# Converter_12V-3V3.net
KiCad netlist of a schematic drawn in Altium Designer
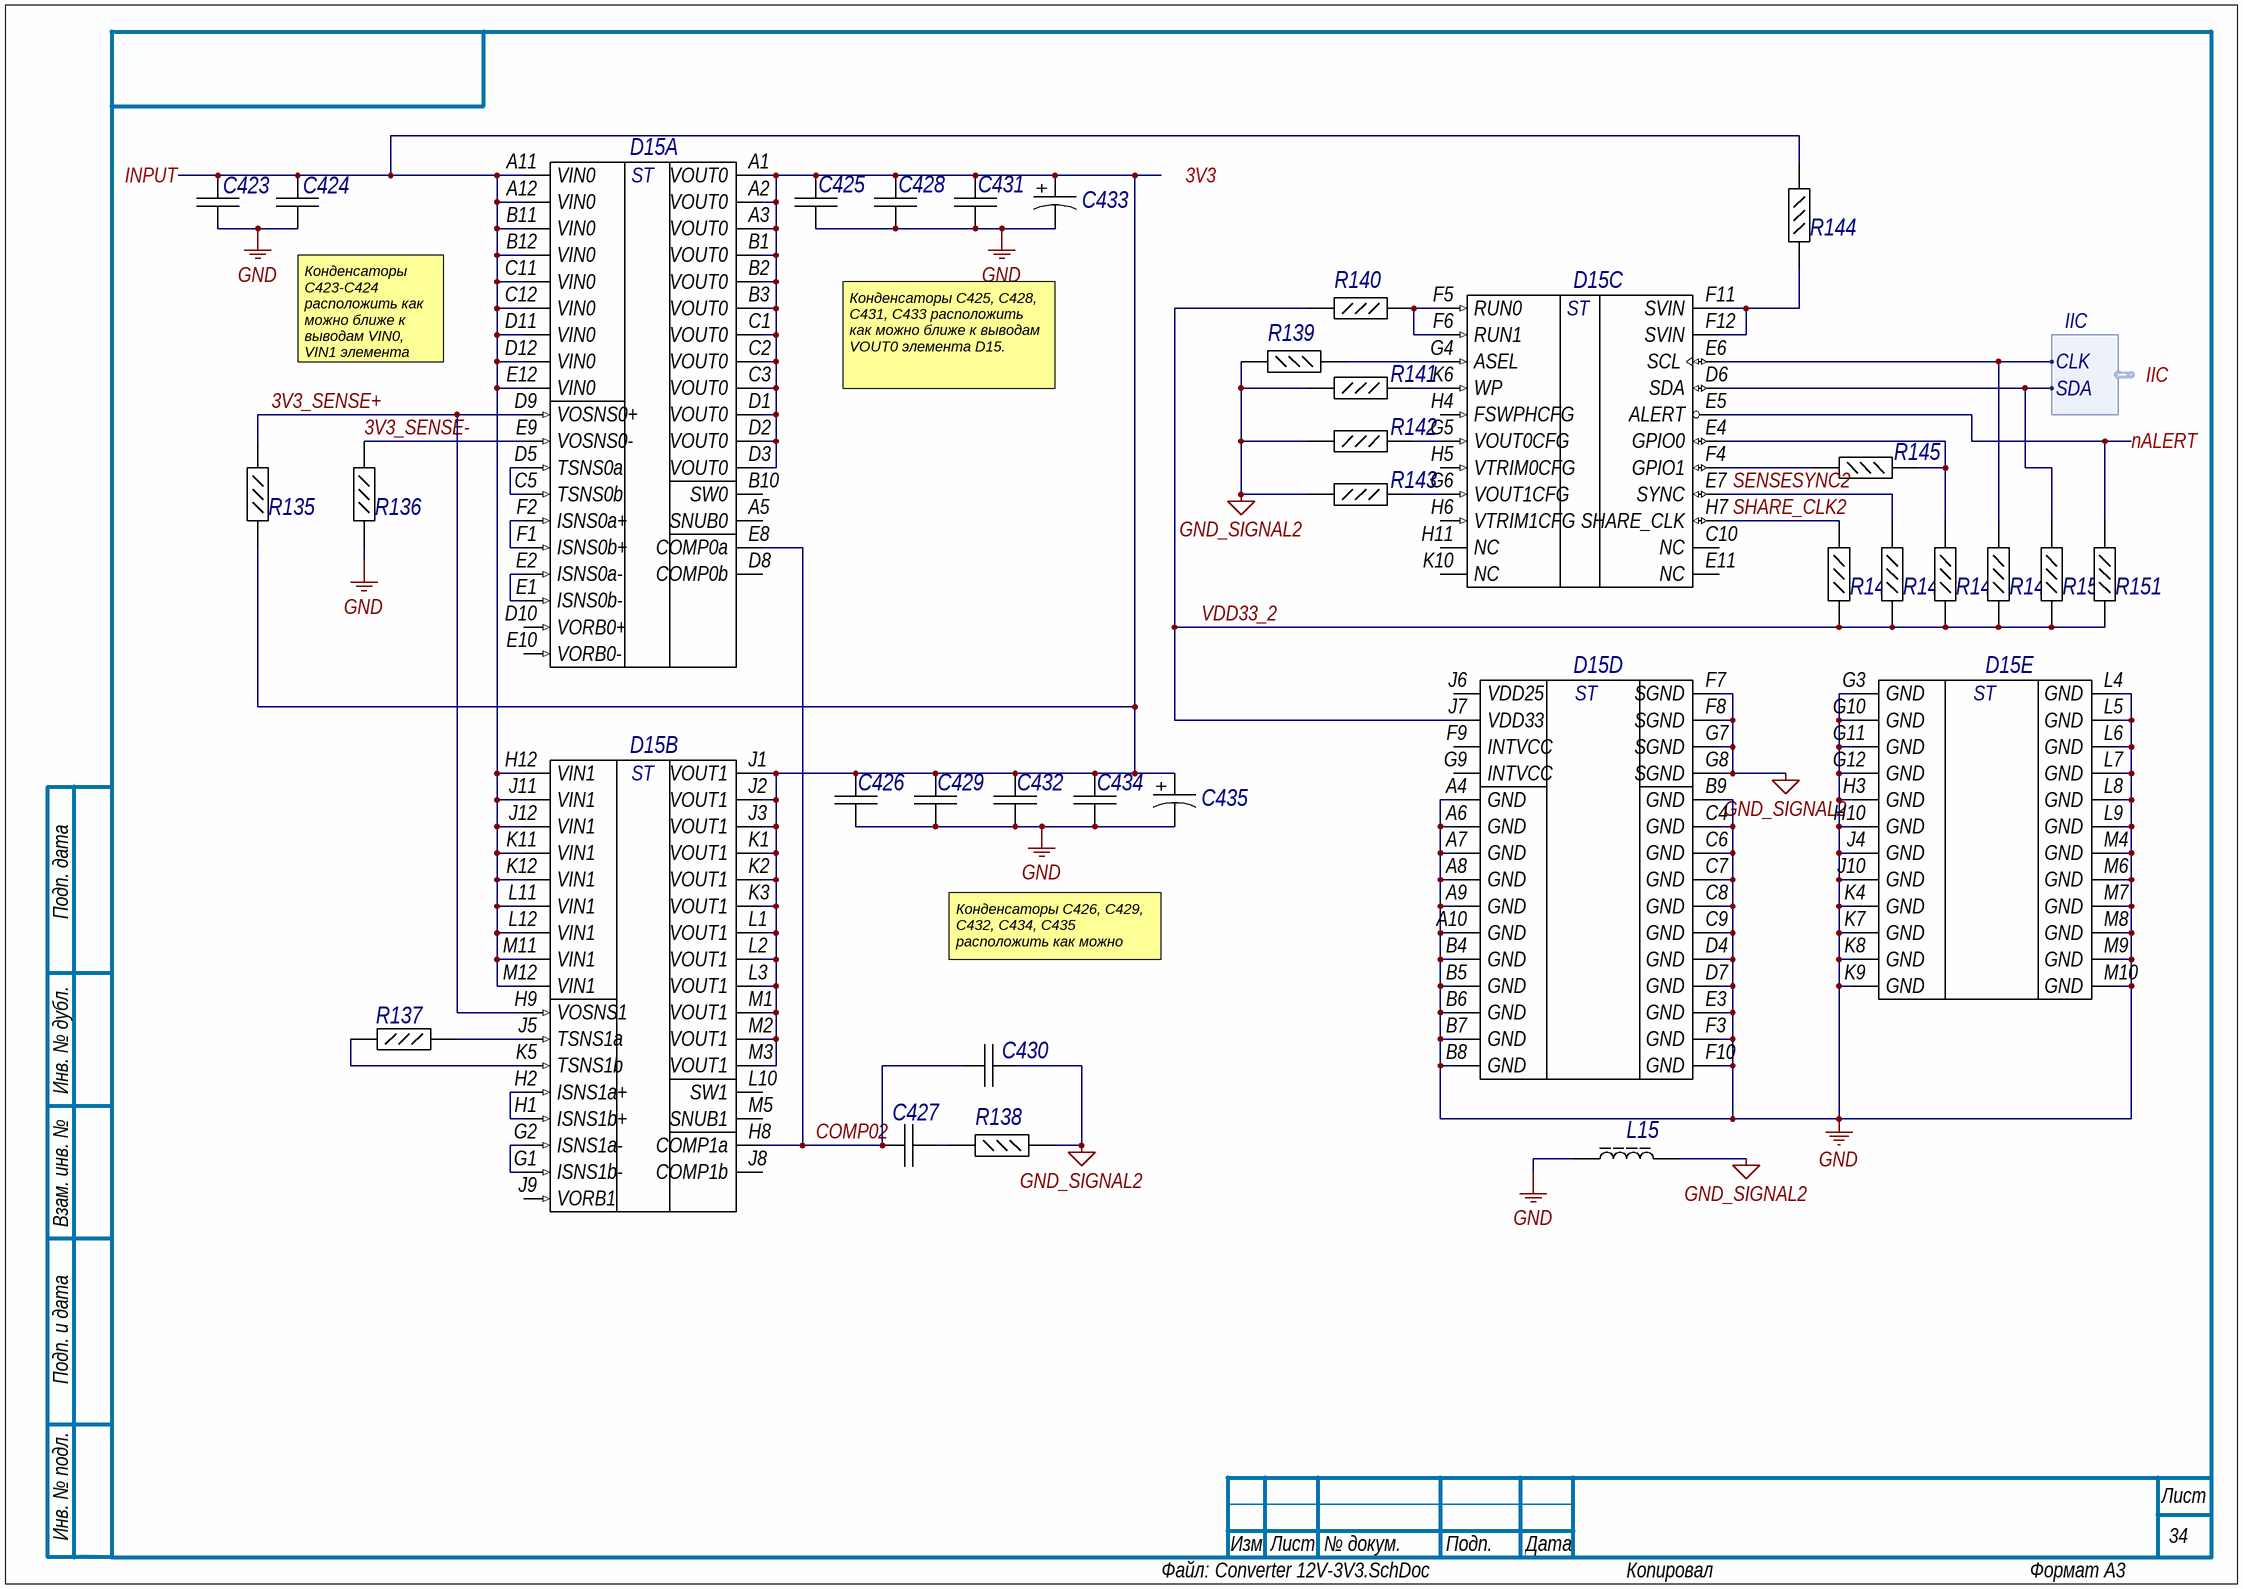
[diagram p0: Converter 12V-3V3.SchDoc]

(export (version "E")
  (design (tool "Eeschema 10.0.6"))
  (components
    (comp (ref "C423")
      (value "GRM31CR61E226KE15L")
      (footprint "CAPC3216X180X55ML20T25")
      (description "Chip Capacitor, 22 uF, +/- 10%, 25 V, -55 to 85 degC, 1206 (3216 Metric), RoHS, Tape and Reel")
      (fields (field (name "TOLERANCE") "10%"))
      (libsource (lib "MiniPC DB") (part "CAP_NP"))
    )
    (comp (ref "C424")
      (value "GRM31CR61E226KE15L")
      (footprint "CAPC3216X180X55ML20T25")
      (description "Chip Capacitor, 22 uF, +/- 10%, 25 V, -55 to 85 degC, 1206 (3216 Metric), RoHS, Tape and Reel")
      (fields (field (name "TOLERANCE") "10%"))
      (libsource (lib "MiniPC DB") (part "CAP_NP"))
    )
    (comp (ref "C425")
      (value "GRM31CR60J107ME39L")
      (footprint "CAPC3216X190X55ML30T25")
      (description "Chip Capacitor, 100 uF, +/- 20%, 6.3 V, -55 to 85 degC, 1206 (3216 Metric), RoHS, Tape and Reel")
      (fields (field (name "TOLERANCE") "20%"))
      (libsource (lib "MiniPC DB") (part "CAP_NP"))
    )
    (comp (ref "C426")
      (value "GRM31CR60J107ME39L")
      (footprint "CAPC3216X190X55ML30T25")
      (description "Chip Capacitor, 100 uF, +/- 20%, 6.3 V, -55 to 85 degC, 1206 (3216 Metric), RoHS, Tape and Reel")
      (fields (field (name "TOLERANCE") "20%"))
      (libsource (lib "MiniPC DB") (part "CAP_NP"))
    )
    (comp (ref "C427")
      (value "CGJ2B2X7R1E222K050BA")
      (footprint "CAPC1005X55X10ML05")
      (description "Chip Capacitor, 2.2 nF, +/- 10%, 25 V, -55 to 125 degC, 0402 (1005 Metric), RoHS, Tape and Reel")
      (fields (field (name "TOLERANCE") "10%"))
      (libsource (lib "MiniPC DB") (part "CAP_NP"))
    )
    (comp (ref "C428")
      (value "GRM31CR60J107ME39L")
      (footprint "CAPC3216X190X55ML30T25")
      (description "Chip Capacitor, 100 uF, +/- 20%, 6.3 V, -55 to 85 degC, 1206 (3216 Metric), RoHS, Tape and Reel")
      (fields (field (name "TOLERANCE") "20%"))
      (libsource (lib "MiniPC DB") (part "CAP_NP"))
    )
    (comp (ref "C429")
      (value "GRM31CR60J107ME39L")
      (footprint "CAPC3216X190X55ML30T25")
      (description "Chip Capacitor, 100 uF, +/- 20%, 6.3 V, -55 to 85 degC, 1206 (3216 Metric), RoHS, Tape and Reel")
      (fields (field (name "TOLERANCE") "20%"))
      (libsource (lib "MiniPC DB") (part "CAP_NP"))
    )
    (comp (ref "C430")
      (value "ECJ-0EC1H680J")
      (footprint "CAPC1005X55X20ML5T10")
      (description "Chip Capacitor, 68 pF, +/- 5%, 50 V, -55 to 125 degC, 0402 (1005 Metric), RoHS, Tape and Reel")
      (fields (field (name "TOLERANCE") "5%"))
      (libsource (lib "MiniPC DB") (part "CAP_NP"))
    )
    (comp (ref "C431")
      (value "GRM31CR60J107ME39L")
      (footprint "CAPC3216X190X55ML30T25")
      (description "Chip Capacitor, 100 uF, +/- 20%, 6.3 V, -55 to 85 degC, 1206 (3216 Metric), RoHS, Tape and Reel")
      (fields (field (name "TOLERANCE") "20%"))
      (libsource (lib "MiniPC DB") (part "CAP_NP"))
    )
    (comp (ref "C432")
      (value "GRM31CR60J107ME39L")
      (footprint "CAPC3216X190X55ML30T25")
      (description "Chip Capacitor, 100 uF, +/- 20%, 6.3 V, -55 to 85 degC, 1206 (3216 Metric), RoHS, Tape and Reel")
      (fields (field (name "TOLERANCE") "20%"))
      (libsource (lib "MiniPC DB") (part "CAP_NP"))
    )
    (comp (ref "C433")
      (value "6TPF330M9L")
      (footprint "PNSC-TPF-D3L_V")
      (description "Tantalum Capacitor, 330 uF, +/- 20%, 6.3 V, -55 to 105 degC, 2-Pin Molded, RoHS, Tape and Reel")
      (libsource (lib "MiniPC DB") (part "CAP_P"))
    )
    (comp (ref "C434")
      (value "GRM31CR60J107ME39L")
      (footprint "CAPC3216X190X55ML30T25")
      (description "Chip Capacitor, 100 uF, +/- 20%, 6.3 V, -55 to 85 degC, 1206 (3216 Metric), RoHS, Tape and Reel")
      (fields (field (name "TOLERANCE") "20%"))
      (libsource (lib "MiniPC DB") (part "CAP_NP"))
    )
    (comp (ref "C435")
      (value "6TPF330M9L")
      (footprint "PNSC-TPF-D3L_V")
      (description "Tantalum Capacitor, 330 uF, +/- 20%, 6.3 V, -55 to 105 degC, 2-Pin Molded, RoHS, Tape and Reel")
      (libsource (lib "MiniPC DB") (part "CAP_P"))
    )
    (comp (ref "D15")
      (value "LTM4676IY#PBF")
      (footprint "LT-BGA-144-05-08-1920_V")
      (libsource (lib "MiniPC DB") (part "LTM4676"))
    )
    (comp (ref "L15")
      (value "742792609")
      (footprint "SMD-0603")
      (description "SMD EMI Suppression Ferrite Bead WE-CBF, Z = 30 Ohm")
      (libsource (lib "MiniPC DB") (part "Choke"))
    )
    (comp (ref "R135")
      (value "ERJ-2GE0R00X")
      (footprint "RESC1005X40X25LL05T05")
      (description "Chip Resistor, 0 mOhm, +/- 5%, 100 mW, -55 to 155 degC, 0402 (1005 Metric), RoHS, Tape and Reel")
      (fields (field (name "TOLERANCE") "5%") (field (name "MANUFACTURER") "Basic Passives"))
      (libsource (lib "MiniPC DB") (part "RES-0.05"))
    )
    (comp (ref "R136")
      (value "ERJ-2GE0R00X")
      (footprint "RESC1005X40X25LL05T05")
      (description "Chip Resistor, 0 mOhm, +/- 5%, 100 mW, -55 to 155 degC, 0402 (1005 Metric), RoHS, Tape and Reel")
      (fields (field (name "TOLERANCE") "5%") (field (name "MANUFACTURER") "Basic Passives"))
      (libsource (lib "MiniPC DB") (part "RES-0.05"))
    )
    (comp (ref "R137")
      (value "ERJ-2GE0R00X")
      (footprint "RESC1005X40X25LL05T05")
      (description "Chip Resistor, 0 mOhm, +/- 5%, 100 mW, -55 to 155 degC, 0402 (1005 Metric), RoHS, Tape and Reel")
      (fields (field (name "TOLERANCE") "5%") (field (name "MANUFACTURER") "Basic Passives"))
      (libsource (lib "") (part "RES-0.05_2"))
    )
    (comp (ref "R138")
      (value "ERJ-2RKF4751X")
      (footprint "RESC1005X40X25LL05T05")
      (description "Chip Resistor, 4.75 KOhm, +/- 1%, 100 mW, -55 to 155 degC, 0402 (1005 Metric), RoHS, Tape and Reel")
      (fields (field (name "TOLERANCE") "1%") (field (name "MANUFACTURER") "Basic Passives"))
      (libsource (lib "MiniPC DB") (part "RES-0.05"))
    )
    (comp (ref "R139")
      (value "CRCW040222K6FKED")
      (footprint "RESC1005X40X25LL05T05")
      (description "Chip Resistor, 22.6 KOhm, +/- 1%, 63 mW, -55 to 155 degC, 0402 (1005 Metric), RoHS, Tape and Reel")
      (fields (field (name "TOLERANCE") "1%"))
      (libsource (lib "") (part "RES-0.05_1"))
    )
    (comp (ref "R140")
      (value "ERJ-2RKF1002X")
      (footprint "RESC1005X40X25LL05T05")
      (description "Chip Resistor, 10 KOhm, +/- 1%, 100 mW, -55 to 155 degC, 0402 (1005 Metric), RoHS, Tape and Reel")
      (fields (field (name "TOLERANCE") "1%") (field (name "MANUFACTURER") "Basic Passives"))
      (libsource (lib "") (part "RES-0.05_2"))
    )
    (comp (ref "R141")
      (value "ERJ-2RKF1002X")
      (footprint "RESC1005X40X25LL05T05")
      (description "Chip Resistor, 10 KOhm, +/- 1%, 100 mW, -55 to 155 degC, 0402 (1005 Metric), RoHS, Tape and Reel")
      (fields (field (name "TOLERANCE") "1%") (field (name "MANUFACTURER") "Basic Passives"))
      (libsource (lib "") (part "RES-0.05_2"))
    )
    (comp (ref "R142")
      (value "CRCW040222K6FKED")
      (footprint "RESC1005X40X25LL05T05")
      (description "Chip Resistor, 22.6 KOhm, +/- 1%, 63 mW, -55 to 155 degC, 0402 (1005 Metric), RoHS, Tape and Reel")
      (fields (field (name "TOLERANCE") "1%"))
      (libsource (lib "") (part "RES-0.05_2"))
    )
    (comp (ref "R143")
      (value "CRCW040222K6FKED")
      (footprint "RESC1005X40X25LL05T05")
      (description "Chip Resistor, 22.6 KOhm, +/- 1%, 63 mW, -55 to 155 degC, 0402 (1005 Metric), RoHS, Tape and Reel")
      (fields (field (name "TOLERANCE") "1%"))
      (libsource (lib "") (part "RES-0.05_2"))
    )
    (comp (ref "R144")
      (value "ERJ-2GE0R00X")
      (footprint "RESC1005X40X25LL05T05")
      (description "Chip Resistor, 0 mOhm, +/- 5%, 100 mW, -55 to 155 degC, 0402 (1005 Metric), RoHS, Tape and Reel")
      (fields (field (name "TOLERANCE") "5%") (field (name "MANUFACTURER") "Basic Passives"))
      (libsource (lib "") (part "RES-0.05_3"))
    )
    (comp (ref "R145")
      (value "ERJ-2GE0R00X")
      (footprint "RESC1005X40X25LL05T05")
      (description "Chip Resistor, 0 mOhm, +/- 5%, 100 mW, -55 to 155 degC, 0402 (1005 Metric), RoHS, Tape and Reel")
      (fields (field (name "TOLERANCE") "5%") (field (name "MANUFACTURER") "Basic Passives"))
      (libsource (lib "") (part "RES-0.05_1"))
    )
    (comp (ref "R146")
      (value "ERJ-2RKF1002X")
      (footprint "RESC1005X40X25LL05T05")
      (description "Chip Resistor, 10 KOhm, +/- 1%, 100 mW, -55 to 155 degC, 0402 (1005 Metric), RoHS, Tape and Reel")
      (fields (field (name "TOLERANCE") "1%") (field (name "MANUFACTURER") "Basic Passives"))
      (libsource (lib "MiniPC DB") (part "RES-0.05"))
    )
    (comp (ref "R147")
      (value "ERJ-2RKF1002X")
      (footprint "RESC1005X40X25LL05T05")
      (description "Chip Resistor, 10 KOhm, +/- 1%, 100 mW, -55 to 155 degC, 0402 (1005 Metric), RoHS, Tape and Reel")
      (fields (field (name "TOLERANCE") "1%") (field (name "MANUFACTURER") "Basic Passives"))
      (libsource (lib "MiniPC DB") (part "RES-0.05"))
    )
    (comp (ref "R148")
      (value "ERJ-2RKF1002X")
      (footprint "RESC1005X40X25LL05T05")
      (description "Chip Resistor, 10 KOhm, +/- 1%, 100 mW, -55 to 155 degC, 0402 (1005 Metric), RoHS, Tape and Reel")
      (fields (field (name "TOLERANCE") "1%") (field (name "MANUFACTURER") "Basic Passives"))
      (libsource (lib "MiniPC DB") (part "RES-0.05"))
    )
    (comp (ref "R149")
      (value "ERJ-2RKF1002X")
      (footprint "RESC1005X40X25LL05T05")
      (description "Chip Resistor, 10 KOhm, +/- 1%, 100 mW, -55 to 155 degC, 0402 (1005 Metric), RoHS, Tape and Reel")
      (fields (field (name "TOLERANCE") "1%") (field (name "MANUFACTURER") "Basic Passives"))
      (libsource (lib "MiniPC DB") (part "RES-0.05"))
    )
    (comp (ref "R150")
      (value "ERJ-2RKF1002X")
      (footprint "RESC1005X40X25LL05T05")
      (description "Chip Resistor, 10 KOhm, +/- 1%, 100 mW, -55 to 155 degC, 0402 (1005 Metric), RoHS, Tape and Reel")
      (fields (field (name "TOLERANCE") "1%") (field (name "MANUFACTURER") "Basic Passives"))
      (libsource (lib "MiniPC DB") (part "RES-0.05"))
    )
    (comp (ref "R151")
      (value "ERJ-2RKF1002X")
      (footprint "RESC1005X40X25LL05T05")
      (description "Chip Resistor, 10 KOhm, +/- 1%, 100 mW, -55 to 155 degC, 0402 (1005 Metric), RoHS, Tape and Reel")
      (fields (field (name "TOLERANCE") "1%") (field (name "MANUFACTURER") "Basic Passives"))
      (libsource (lib "MiniPC DB") (part "RES-0.05"))
    )
  )
  (nets
    (net (code "2") (name "/3V3") (class "Default")
      (node (ref "C425") (pin "2") (pinfunction "2_2") (pintype "passive"))
      (node (ref "C426") (pin "2") (pinfunction "2_2") (pintype "passive"))
      (node (ref "C428") (pin "2") (pinfunction "2_2") (pintype "passive"))
      (node (ref "C429") (pin "2") (pinfunction "2_2") (pintype "passive"))
      (node (ref "C431") (pin "2") (pinfunction "2_2") (pintype "passive"))
      (node (ref "C432") (pin "2") (pinfunction "2_2") (pintype "passive"))
      (node (ref "C433") (pin "1") (pinfunction "1_1") (pintype "passive"))
      (node (ref "C434") (pin "2") (pinfunction "2_2") (pintype "passive"))
      (node (ref "C435") (pin "1") (pinfunction "1_1") (pintype "passive"))
      (node (ref "D15") (pin "A1") (pinfunction "VOUT0_A1") (pintype "power_in"))
      (node (ref "D15") (pin "A2") (pinfunction "VOUT0_A2") (pintype "power_in"))
      (node (ref "D15") (pin "A3") (pinfunction "VOUT0_A3") (pintype "power_in"))
      (node (ref "D15") (pin "B1") (pinfunction "VOUT0_B1") (pintype "power_in"))
      (node (ref "D15") (pin "B2") (pinfunction "VOUT0_B2") (pintype "power_in"))
      (node (ref "D15") (pin "B3") (pinfunction "VOUT0_B3") (pintype "power_in"))
      (node (ref "D15") (pin "C1") (pinfunction "VOUT0_C1") (pintype "power_in"))
      (node (ref "D15") (pin "C2") (pinfunction "VOUT0_C2") (pintype "power_in"))
      (node (ref "D15") (pin "C3") (pinfunction "VOUT0_C3") (pintype "power_in"))
      (node (ref "D15") (pin "D1") (pinfunction "VOUT0_D1") (pintype "power_in"))
      (node (ref "D15") (pin "D2") (pinfunction "VOUT0_D2") (pintype "power_in"))
      (node (ref "D15") (pin "D3") (pinfunction "VOUT0_D3") (pintype "power_in"))
      (node (ref "D15") (pin "J1") (pinfunction "VOUT1_J1") (pintype "power_in"))
      (node (ref "D15") (pin "J2") (pinfunction "VOUT1_J2") (pintype "power_in"))
      (node (ref "D15") (pin "J3") (pinfunction "VOUT1_J3") (pintype "power_in"))
      (node (ref "D15") (pin "K1") (pinfunction "VOUT1_K1") (pintype "power_in"))
      (node (ref "D15") (pin "K2") (pinfunction "VOUT1_K2") (pintype "power_in"))
      (node (ref "D15") (pin "K3") (pinfunction "VOUT1_K3") (pintype "power_in"))
      (node (ref "D15") (pin "L1") (pinfunction "VOUT1_L1") (pintype "power_in"))
      (node (ref "D15") (pin "L2") (pinfunction "VOUT1_L2") (pintype "power_in"))
      (node (ref "D15") (pin "L3") (pinfunction "VOUT1_L3") (pintype "power_in"))
      (node (ref "D15") (pin "M1") (pinfunction "VOUT1_M1") (pintype "power_in"))
      (node (ref "D15") (pin "M2") (pinfunction "VOUT1_M2") (pintype "power_in"))
      (node (ref "D15") (pin "M3") (pinfunction "VOUT1_M3") (pintype "power_in"))
      (node (ref "R135") (pin "2") (pinfunction "2_2") (pintype "passive"))
    )
    (net (code "3") (name "/3V3_SENSE+") (class "Default")
      (node (ref "D15") (pin "D9") (pinfunction "VOSNS0+_D9") (pintype "input"))
      (node (ref "D15") (pin "H9") (pinfunction "VOSNS1_H9") (pintype "input"))
      (node (ref "R135") (pin "1") (pinfunction "1_1") (pintype "passive"))
    )
    (net (code "4") (name "/3V3_SENSE-") (class "Default")
      (node (ref "D15") (pin "E9") (pinfunction "VOSNS0-_E9") (pintype "input"))
      (node (ref "R136") (pin "1") (pinfunction "1_1") (pintype "passive"))
    )
    (net (code "5") (name "/COMP02") (class "Default")
      (node (ref "C427") (pin "2") (pinfunction "2_2") (pintype "passive"))
      (node (ref "C430") (pin "2") (pinfunction "2_2") (pintype "passive"))
      (node (ref "D15") (pin "E8") (pinfunction "COMP0a_E8") (pintype "passive"))
      (node (ref "D15") (pin "H8") (pinfunction "COMP1a_H8") (pintype "passive"))
    )
    (net (code "6") (name "/INPUT") (class "Default")
      (node (ref "C423") (pin "2") (pinfunction "2_2") (pintype "passive"))
      (node (ref "C424") (pin "2") (pinfunction "2_2") (pintype "passive"))
      (node (ref "D15") (pin "A11") (pinfunction "VIN0_A11") (pintype "passive"))
      (node (ref "D15") (pin "A12") (pinfunction "VIN0_A12") (pintype "passive"))
      (node (ref "D15") (pin "B11") (pinfunction "VIN0_B11") (pintype "passive"))
      (node (ref "D15") (pin "B12") (pinfunction "VIN0_B12") (pintype "passive"))
      (node (ref "D15") (pin "C11") (pinfunction "VIN0_C11") (pintype "passive"))
      (node (ref "D15") (pin "C12") (pinfunction "VIN0_C12") (pintype "passive"))
      (node (ref "D15") (pin "D11") (pinfunction "VIN0_D11") (pintype "passive"))
      (node (ref "D15") (pin "D12") (pinfunction "VIN0_D12") (pintype "passive"))
      (node (ref "D15") (pin "E12") (pinfunction "VIN0_E12") (pintype "passive"))
      (node (ref "D15") (pin "H12") (pinfunction "VIN1_H12") (pintype "passive"))
      (node (ref "D15") (pin "J11") (pinfunction "VIN1_J11") (pintype "passive"))
      (node (ref "D15") (pin "J12") (pinfunction "VIN1_J12") (pintype "passive"))
      (node (ref "D15") (pin "K11") (pinfunction "VIN1_K11") (pintype "passive"))
      (node (ref "D15") (pin "K12") (pinfunction "VIN1_K12") (pintype "passive"))
      (node (ref "D15") (pin "L11") (pinfunction "VIN1_L11") (pintype "passive"))
      (node (ref "D15") (pin "L12") (pinfunction "VIN1_L12") (pintype "passive"))
      (node (ref "D15") (pin "M11") (pinfunction "VIN1_M11") (pintype "passive"))
      (node (ref "D15") (pin "M12") (pinfunction "VIN1_M12") (pintype "passive"))
      (node (ref "R144") (pin "2") (pinfunction "2_2") (pintype "passive"))
    )
    (net (code "7") (name "/SENSESYNC2") (class "Default")
      (node (ref "D15") (pin "E7") (pinfunction "SYNC_E7") (pintype "bidirectional"))
      (node (ref "R147") (pin "1") (pinfunction "1_1") (pintype "passive"))
    )
    (net (code "8") (name "/SHARE_CLK2") (class "Default")
      (node (ref "D15") (pin "H7") (pinfunction "SHARE_CLK_H7") (pintype "bidirectional"))
      (node (ref "R146") (pin "1") (pinfunction "1_1") (pintype "passive"))
    )
    (net (code "9") (name "/VDD33_2") (class "Default")
      (node (ref "D15") (pin "J7") (pinfunction "VDD33_J7") (pintype "passive"))
      (node (ref "R140") (pin "2") (pinfunction "2_2") (pintype "passive"))
      (node (ref "R146") (pin "2") (pinfunction "2_2") (pintype "passive"))
      (node (ref "R147") (pin "2") (pinfunction "2_2") (pintype "passive"))
      (node (ref "R148") (pin "2") (pinfunction "2_2") (pintype "passive"))
      (node (ref "R149") (pin "2") (pinfunction "2_2") (pintype "passive"))
      (node (ref "R150") (pin "2") (pinfunction "2_2") (pintype "passive"))
      (node (ref "R151") (pin "2") (pinfunction "2_2") (pintype "passive"))
    )
    (net (code "10") (name "/nALERT") (class "Default")
      (node (ref "D15") (pin "E5") (pinfunction "ALERT_E5") (pintype "open_collector"))
      (node (ref "R151") (pin "1") (pinfunction "1_1") (pintype "passive"))
    )
    (net (code "12") (name "GND") (class "Default")
      (node (ref "C423") (pin "1") (pinfunction "1_1") (pintype "passive"))
      (node (ref "C424") (pin "1") (pinfunction "1_1") (pintype "passive"))
      (node (ref "C425") (pin "1") (pinfunction "1_1") (pintype "passive"))
      (node (ref "C426") (pin "1") (pinfunction "1_1") (pintype "passive"))
      (node (ref "C428") (pin "1") (pinfunction "1_1") (pintype "passive"))
      (node (ref "C429") (pin "1") (pinfunction "1_1") (pintype "passive"))
      (node (ref "C431") (pin "1") (pinfunction "1_1") (pintype "passive"))
      (node (ref "C432") (pin "1") (pinfunction "1_1") (pintype "passive"))
      (node (ref "C433") (pin "2") (pinfunction "2_2") (pintype "passive"))
      (node (ref "C434") (pin "1") (pinfunction "1_1") (pintype "passive"))
      (node (ref "C435") (pin "2") (pinfunction "2_2") (pintype "passive"))
      (node (ref "D15") (pin "A10") (pinfunction "GND_A10") (pintype "passive"))
      (node (ref "D15") (pin "A4") (pinfunction "GND_A4") (pintype "passive"))
      (node (ref "D15") (pin "A6") (pinfunction "GND_A6") (pintype "passive"))
      (node (ref "D15") (pin "A7") (pinfunction "GND_A7") (pintype "passive"))
      (node (ref "D15") (pin "A8") (pinfunction "GND_A8") (pintype "passive"))
      (node (ref "D15") (pin "A9") (pinfunction "GND_A9") (pintype "passive"))
      (node (ref "D15") (pin "B4") (pinfunction "GND_B4") (pintype "passive"))
      (node (ref "D15") (pin "B5") (pinfunction "GND_B5") (pintype "passive"))
      (node (ref "D15") (pin "B6") (pinfunction "GND_B6") (pintype "passive"))
      (node (ref "D15") (pin "B7") (pinfunction "GND_B7") (pintype "passive"))
      (node (ref "D15") (pin "B8") (pinfunction "GND_B8") (pintype "passive"))
      (node (ref "D15") (pin "B9") (pinfunction "GND_B9") (pintype "passive"))
      (node (ref "D15") (pin "C4") (pinfunction "GND_C4") (pintype "passive"))
      (node (ref "D15") (pin "C6") (pinfunction "GND_C6") (pintype "passive"))
      (node (ref "D15") (pin "C7") (pinfunction "GND_C7") (pintype "passive"))
      (node (ref "D15") (pin "C8") (pinfunction "GND_C8") (pintype "passive"))
      (node (ref "D15") (pin "C9") (pinfunction "GND_C9") (pintype "passive"))
      (node (ref "D15") (pin "D4") (pinfunction "GND_D4") (pintype "passive"))
      (node (ref "D15") (pin "D7") (pinfunction "GND_D7") (pintype "passive"))
      (node (ref "D15") (pin "E3") (pinfunction "GND_E3") (pintype "passive"))
      (node (ref "D15") (pin "F10") (pinfunction "GND_F10") (pintype "passive"))
      (node (ref "D15") (pin "F3") (pinfunction "GND_F3") (pintype "passive"))
      (node (ref "D15") (pin "G10") (pinfunction "GND_G10") (pintype "passive"))
      (node (ref "D15") (pin "G11") (pinfunction "GND_G11") (pintype "passive"))
      (node (ref "D15") (pin "G12") (pinfunction "GND_G12") (pintype "passive"))
      (node (ref "D15") (pin "G3") (pinfunction "GND_G3") (pintype "passive"))
      (node (ref "D15") (pin "H10") (pinfunction "GND_H10") (pintype "passive"))
      (node (ref "D15") (pin "H3") (pinfunction "GND_H3") (pintype "passive"))
      (node (ref "D15") (pin "J10") (pinfunction "GND_J10") (pintype "passive"))
      (node (ref "D15") (pin "J4") (pinfunction "GND_J4") (pintype "passive"))
      (node (ref "D15") (pin "K4") (pinfunction "GND_K4") (pintype "passive"))
      (node (ref "D15") (pin "K7") (pinfunction "GND_K7") (pintype "passive"))
      (node (ref "D15") (pin "K8") (pinfunction "GND_K8") (pintype "passive"))
      (node (ref "D15") (pin "K9") (pinfunction "GND_K9") (pintype "passive"))
      (node (ref "D15") (pin "L4") (pinfunction "GND_L4") (pintype "passive"))
      (node (ref "D15") (pin "L5") (pinfunction "GND_L5") (pintype "passive"))
      (node (ref "D15") (pin "L6") (pinfunction "GND_L6") (pintype "passive"))
      (node (ref "D15") (pin "L7") (pinfunction "GND_L7") (pintype "passive"))
      (node (ref "D15") (pin "L8") (pinfunction "GND_L8") (pintype "passive"))
      (node (ref "D15") (pin "L9") (pinfunction "GND_L9") (pintype "passive"))
      (node (ref "D15") (pin "M10") (pinfunction "GND_M10") (pintype "passive"))
      (node (ref "D15") (pin "M4") (pinfunction "GND_M4") (pintype "passive"))
      (node (ref "D15") (pin "M6") (pinfunction "GND_M6") (pintype "passive"))
      (node (ref "D15") (pin "M7") (pinfunction "GND_M7") (pintype "passive"))
      (node (ref "D15") (pin "M8") (pinfunction "GND_M8") (pintype "passive"))
      (node (ref "D15") (pin "M9") (pinfunction "GND_M9") (pintype "passive"))
      (node (ref "L15") (pin "1") (pinfunction "1_1") (pintype "passive"))
      (node (ref "R136") (pin "2") (pinfunction "2_2") (pintype "passive"))
    )
    (net (code "13") (name "GND_SIGNAL2") (class "Default")
      (node (ref "C430") (pin "1") (pinfunction "1_1") (pintype "passive"))
      (node (ref "D15") (pin "F7") (pinfunction "SGND_F7") (pintype "passive"))
      (node (ref "D15") (pin "F8") (pinfunction "SGND_F8") (pintype "passive"))
      (node (ref "D15") (pin "G7") (pinfunction "SGND_G7") (pintype "passive"))
      (node (ref "D15") (pin "G8") (pinfunction "SGND_G8") (pintype "passive"))
      (node (ref "L15") (pin "2") (pinfunction "2_2") (pintype "passive"))
      (node (ref "R138") (pin "1") (pinfunction "1_1") (pintype "passive"))
      (node (ref "R139") (pin "1") (pinfunction "1_1") (pintype "passive"))
      (node (ref "R141") (pin "2") (pinfunction "2_2") (pintype "passive"))
      (node (ref "R142") (pin "2") (pinfunction "2_2") (pintype "passive"))
      (node (ref "R143") (pin "2") (pinfunction "2_2") (pintype "passive"))
    )
    (net (code "14") (name "Net-(C427-Pad1)") (class "Default")
      (node (ref "C427") (pin "1") (pinfunction "1_1") (pintype "passive"))
      (node (ref "R138") (pin "2") (pinfunction "2_2") (pintype "passive"))
    )
    (net (code "15") (name "Net-(D15A-ISNS0a+)") (class "Default")
      (node (ref "D15") (pin "F1") (pinfunction "ISNS0b+_F1") (pintype "input"))
      (node (ref "D15") (pin "F2") (pinfunction "ISNS0a+_F2") (pintype "input"))
    )
    (net (code "16") (name "Net-(D15A-ISNS0a-)") (class "Default")
      (node (ref "D15") (pin "E1") (pinfunction "ISNS0b-_E1") (pintype "input"))
      (node (ref "D15") (pin "E2") (pinfunction "ISNS0a-_E2") (pintype "input"))
    )
    (net (code "17") (name "Net-(D15A-TSNS0a)") (class "Default")
      (node (ref "D15") (pin "C5") (pinfunction "TSNS0b_C5") (pintype "input"))
      (node (ref "D15") (pin "D5") (pinfunction "TSNS0a_D5") (pintype "input"))
    )
    (net (code "18") (name "Net-(D15B-ISNS1a+)") (class "Default")
      (node (ref "D15") (pin "H1") (pinfunction "ISNS1b+_H1") (pintype "input"))
      (node (ref "D15") (pin "H2") (pinfunction "ISNS1a+_H2") (pintype "input"))
    )
    (net (code "19") (name "Net-(D15B-ISNS1a-)") (class "Default")
      (node (ref "D15") (pin "G1") (pinfunction "ISNS1b-_G1") (pintype "input"))
      (node (ref "D15") (pin "G2") (pinfunction "ISNS1a-_G2") (pintype "input"))
    )
    (net (code "20") (name "Net-(D15B-TSNS1a)") (class "Default")
      (node (ref "D15") (pin "J5") (pinfunction "TSNS1a_J5") (pintype "input"))
      (node (ref "R137") (pin "1") (pinfunction "1_1") (pintype "passive"))
    )
    (net (code "21") (name "Net-(D15B-TSNS1b)") (class "Default")
      (node (ref "D15") (pin "K5") (pinfunction "TSNS1b_K5") (pintype "input"))
      (node (ref "R137") (pin "2") (pinfunction "2_2") (pintype "passive"))
    )
    (net (code "22") (name "Net-(D15C-ASEL)") (class "Default")
      (node (ref "D15") (pin "G4") (pinfunction "ASEL_G4") (pintype "input"))
      (node (ref "R139") (pin "2") (pinfunction "2_2") (pintype "passive"))
    )
    (net (code "23") (name "Net-(D15C-GPIO0)") (class "Default")
      (node (ref "D15") (pin "E4") (pinfunction "GPIO0_E4") (pintype "bidirectional"))
      (node (ref "R145") (pin "2") (pinfunction "2_2") (pintype "passive"))
      (node (ref "R148") (pin "1") (pinfunction "1_1") (pintype "passive"))
    )
    (net (code "24") (name "Net-(D15C-GPIO1)") (class "Default")
      (node (ref "D15") (pin "F4") (pinfunction "GPIO1_F4") (pintype "bidirectional"))
      (node (ref "R145") (pin "1") (pinfunction "1_1") (pintype "passive"))
    )
    (net (code "25") (name "Net-(D15C-RUN0)") (class "Default")
      (node (ref "D15") (pin "F5") (pinfunction "RUN0_F5") (pintype "input"))
      (node (ref "D15") (pin "F6") (pinfunction "RUN1_F6") (pintype "input"))
      (node (ref "R140") (pin "1") (pinfunction "1_1") (pintype "passive"))
    )
    (net (code "26") (name "Net-(D15C-SCL)") (class "Default")
      (node (ref "D15") (pin "E6") (pinfunction "SCL_E6") (pintype "bidirectional"))
      (node (ref "R149") (pin "1") (pinfunction "1_1") (pintype "passive"))
    )
    (net (code "27") (name "Net-(D15C-SDA)") (class "Default")
      (node (ref "D15") (pin "D6") (pinfunction "SDA_D6") (pintype "bidirectional"))
      (node (ref "R150") (pin "1") (pinfunction "1_1") (pintype "passive"))
    )
    (net (code "28") (name "Net-(D15C-SVIN-PadF11)") (class "Default")
      (node (ref "D15") (pin "F11") (pinfunction "SVIN_F11") (pintype "power_in"))
      (node (ref "D15") (pin "F12") (pinfunction "SVIN_F12") (pintype "power_in"))
      (node (ref "R144") (pin "1") (pinfunction "1_1") (pintype "passive"))
    )
    (net (code "29") (name "Net-(D15C-VOUT0CFG)") (class "Default")
      (node (ref "D15") (pin "G5") (pinfunction "VOUT0CFG_G5") (pintype "input"))
      (node (ref "R142") (pin "1") (pinfunction "1_1") (pintype "passive"))
    )
    (net (code "30") (name "Net-(D15C-VOUT1CFG)") (class "Default")
      (node (ref "D15") (pin "G6") (pinfunction "VOUT1CFG_G6") (pintype "input"))
      (node (ref "R143") (pin "1") (pinfunction "1_1") (pintype "passive"))
    )
    (net (code "31") (name "Net-(D15C-WP)") (class "Default")
      (node (ref "D15") (pin "K6") (pinfunction "WP_K6") (pintype "input"))
      (node (ref "R141") (pin "1") (pinfunction "1_1") (pintype "passive"))
    )
    (net (code "32") (name "unconnected-(D15A-COMP0b-PadD8)") (class "Default")
      (node (ref "D15") (pin "D8") (pinfunction "COMP0b_D8") (pintype "passive"))
    )
    (net (code "33") (name "unconnected-(D15A-SNUB0-PadA5)") (class "Default")
      (node (ref "D15") (pin "A5") (pinfunction "SNUB0_A5") (pintype "passive"))
    )
    (net (code "34") (name "unconnected-(D15A-SW0-PadB10)") (class "Default")
      (node (ref "D15") (pin "B10") (pinfunction "SW0_B10") (pintype "passive"))
    )
    (net (code "35") (name "unconnected-(D15A-VORB0+-PadD10)") (class "Default")
      (node (ref "D15") (pin "D10") (pinfunction "VORB0+_D10") (pintype "input"))
    )
    (net (code "36") (name "unconnected-(D15A-VORB0--PadE10)") (class "Default")
      (node (ref "D15") (pin "E10") (pinfunction "VORB0-_E10") (pintype "input"))
    )
    (net (code "37") (name "unconnected-(D15B-COMP1b-PadJ8)") (class "Default")
      (node (ref "D15") (pin "J8") (pinfunction "COMP1b_J8") (pintype "passive"))
    )
    (net (code "38") (name "unconnected-(D15B-SNUB1-PadM5)") (class "Default")
      (node (ref "D15") (pin "M5") (pinfunction "SNUB1_M5") (pintype "passive"))
    )
    (net (code "39") (name "unconnected-(D15B-SW1-PadL10)") (class "Default")
      (node (ref "D15") (pin "L10") (pinfunction "SW1_L10") (pintype "passive"))
    )
    (net (code "40") (name "unconnected-(D15B-VORB1-PadJ9)") (class "Default")
      (node (ref "D15") (pin "J9") (pinfunction "VORB1_J9") (pintype "input"))
    )
    (net (code "41") (name "unconnected-(D15C-FSWPHCFG-PadH4)") (class "Default")
      (node (ref "D15") (pin "H4") (pinfunction "FSWPHCFG_H4") (pintype "input"))
    )
    (net (code "42") (name "unconnected-(D15C-NC-PadC10)") (class "Default")
      (node (ref "D15") (pin "C10") (pinfunction "NC_C10") (pintype "passive"))
    )
    (net (code "43") (name "unconnected-(D15C-NC-PadE11)") (class "Default")
      (node (ref "D15") (pin "E11") (pinfunction "NC_E11") (pintype "passive"))
    )
    (net (code "44") (name "unconnected-(D15C-NC-PadH11)") (class "Default")
      (node (ref "D15") (pin "H11") (pinfunction "NC_H11") (pintype "passive"))
    )
    (net (code "45") (name "unconnected-(D15C-NC-PadK10)") (class "Default")
      (node (ref "D15") (pin "K10") (pinfunction "NC_K10") (pintype "passive"))
    )
    (net (code "46") (name "unconnected-(D15C-VTRIM0CFG-PadH5)") (class "Default")
      (node (ref "D15") (pin "H5") (pinfunction "VTRIM0CFG_H5") (pintype "input"))
    )
    (net (code "47") (name "unconnected-(D15C-VTRIM1CFG-PadH6)") (class "Default")
      (node (ref "D15") (pin "H6") (pinfunction "VTRIM1CFG_H6") (pintype "input"))
    )
    (net (code "48") (name "unconnected-(D15D-INTVCC-PadF9)") (class "Default")
      (node (ref "D15") (pin "F9") (pinfunction "INTVCC_F9") (pintype "passive"))
    )
    (net (code "49") (name "unconnected-(D15D-INTVCC-PadG9)") (class "Default")
      (node (ref "D15") (pin "G9") (pinfunction "INTVCC_G9") (pintype "passive"))
    )
    (net (code "50") (name "unconnected-(D15D-VDD25-PadJ6)") (class "Default")
      (node (ref "D15") (pin "J6") (pinfunction "VDD25_J6") (pintype "passive"))
    )
  )
)
